# SCH_Konwerter-Hal-Elektrody_2026-02-04.net
KiCad netlist of a schematic drawn in EasyEDA
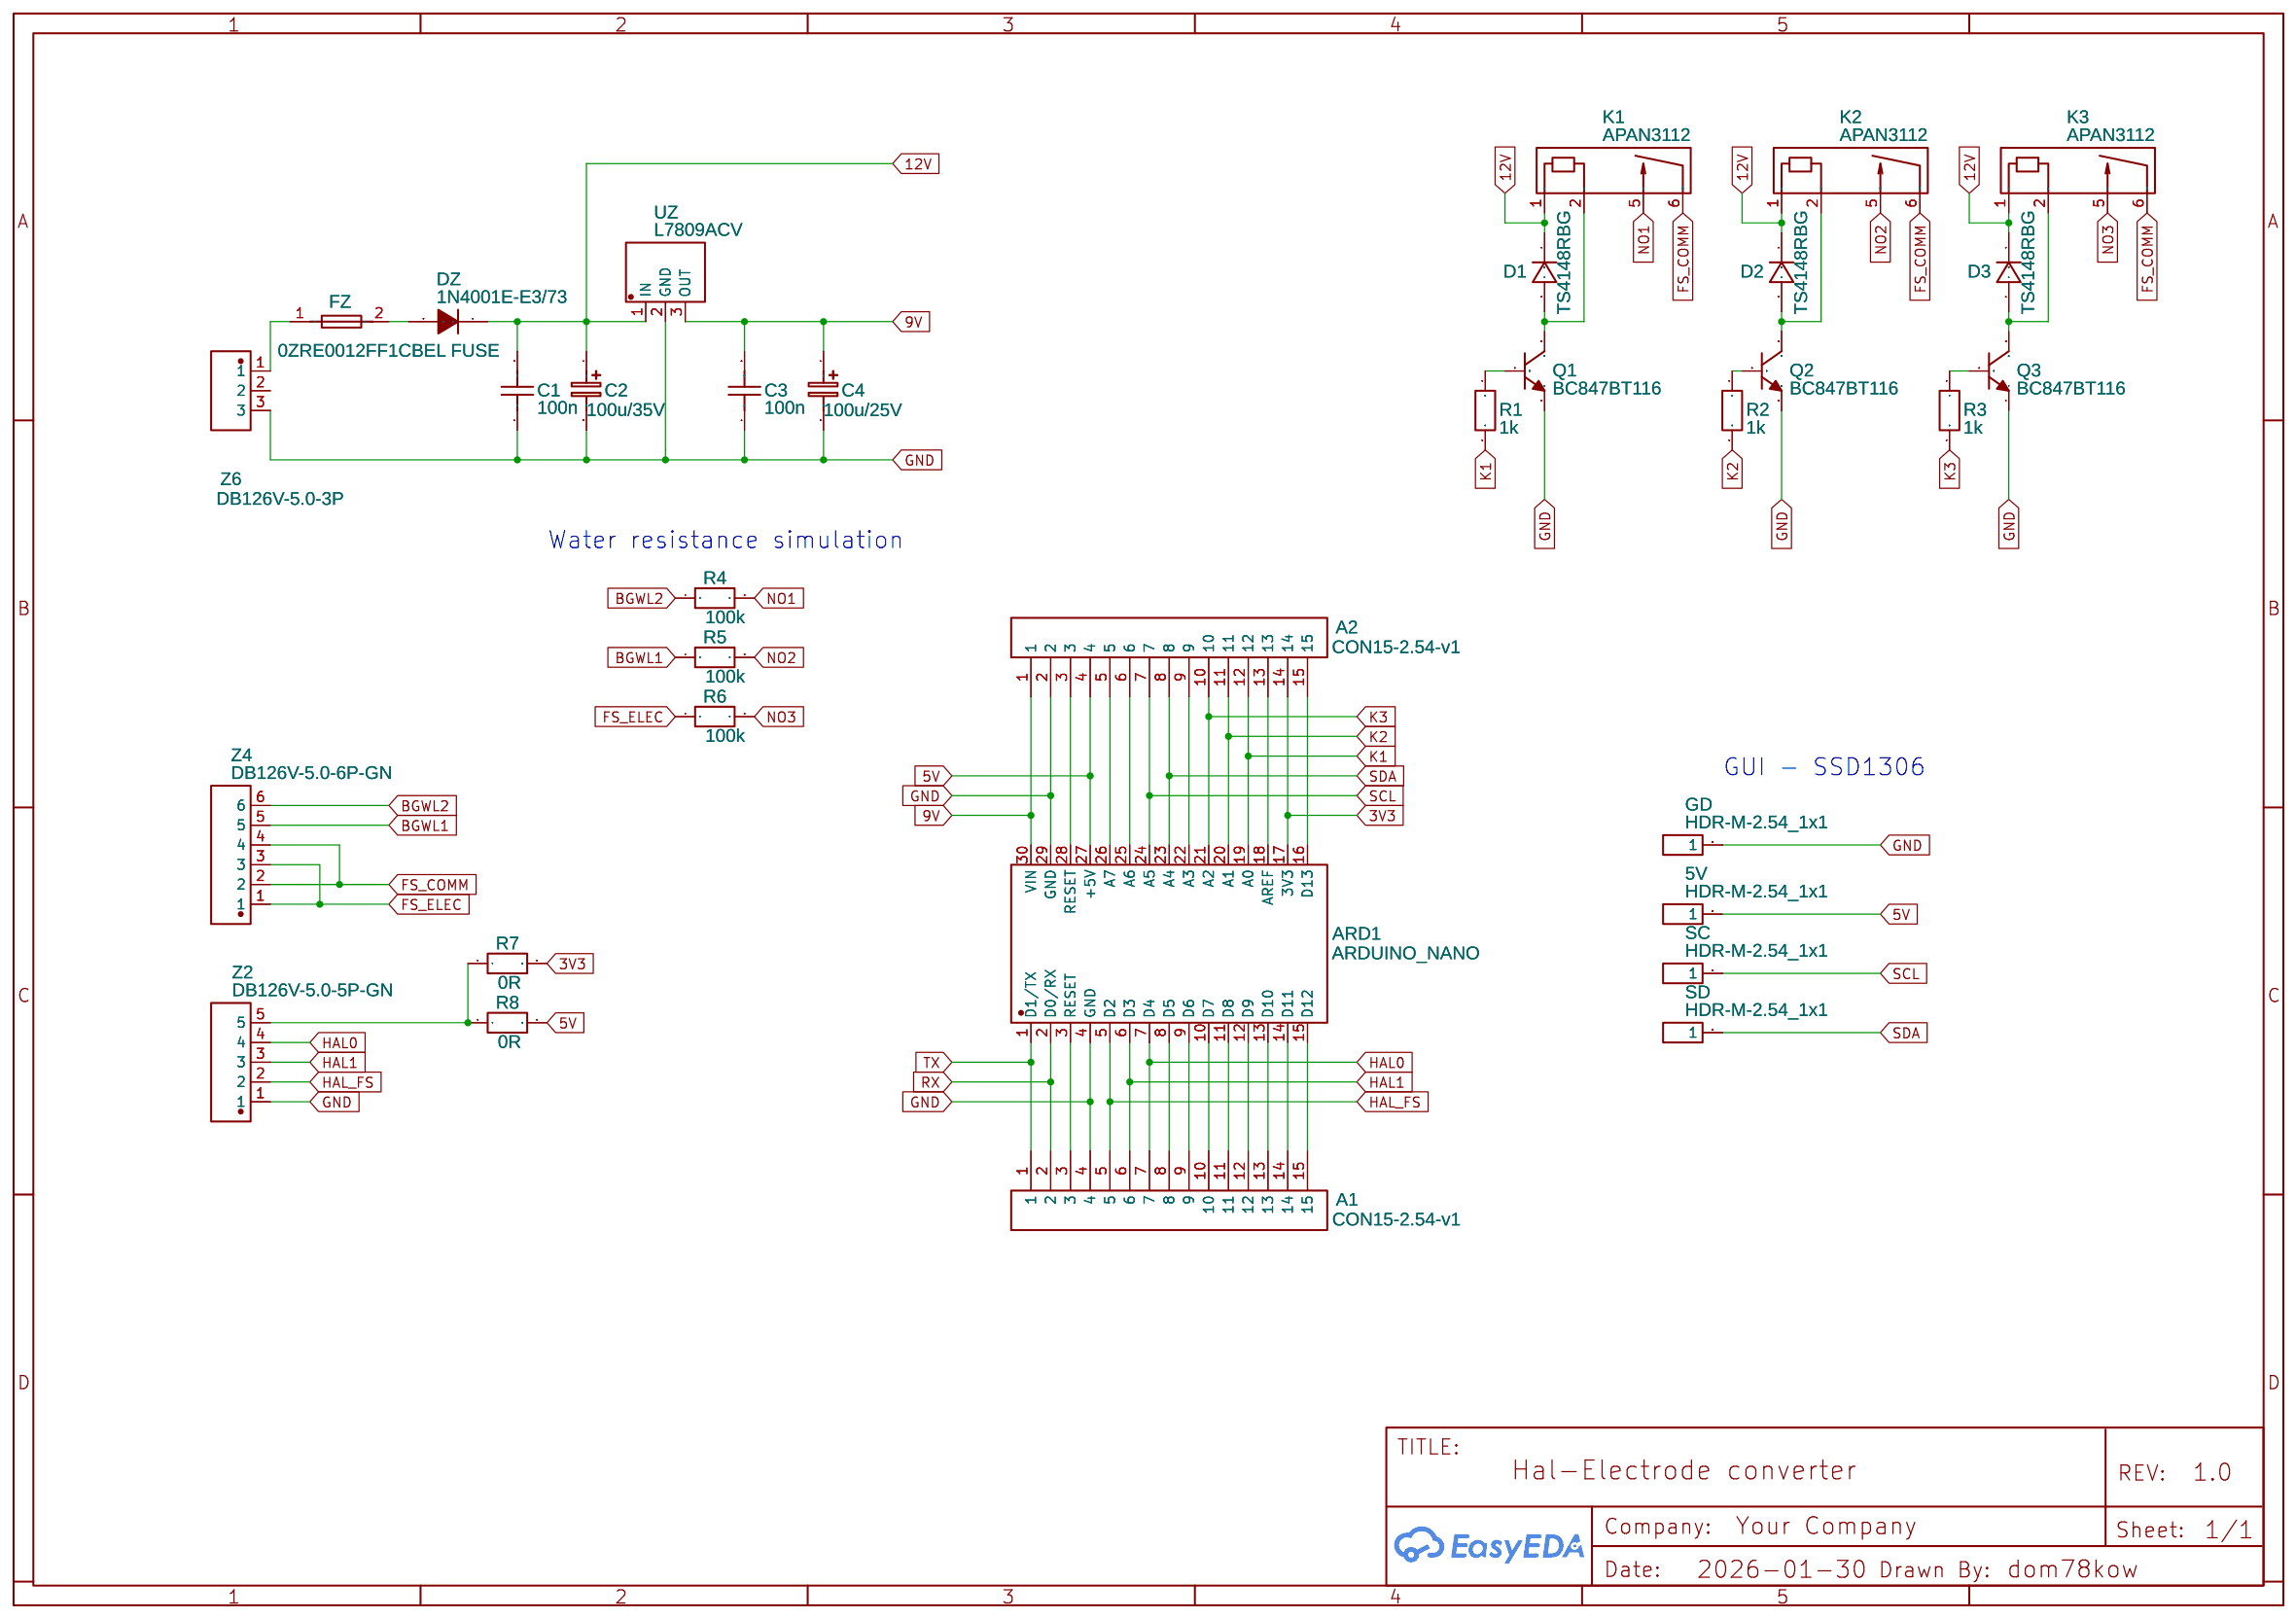
[diagram p0: schematic sheet]

(export (version "E")
  (design (tool "Eeschema 10.0.6"))
  (components
    (comp (ref "5V") (value "HDR-M-2.54_1x1") (libsource (lib "") (part "HDR-M-2.54_1x1_3")))
    (comp (ref "A1") (value "CON15-2.54-v1") (libsource (lib "") (part "CON15-2.54-v1_1")))
    (comp (ref "A2") (value "CON15-2.54-v1") (libsource (lib "") (part "CON15-2.54-v1")))
    (comp (ref "ARD1") (value "ARDUINO_NANO") (libsource (lib "") (part "ARDUINO_NANO")))
    (comp (ref "C1") (value "100n") (libsource (lib "") (part "C_1206_US")))
    (comp (ref "C2") (value "100u/35V") (libsource (lib "") (part "CE_TH_D5.0×F2.0_EU")))
    (comp (ref "C3") (value "100n") (libsource (lib "") (part "C_1206_US")))
    (comp (ref "C4") (value "100u/25V") (libsource (lib "") (part "CE_TH_D5.0×F2.0_EU")))
    (comp (ref "D1")
      (value "TS4148RBG")
      (fields (field (name "Manufacturer Part") "CD4148WP") (field (name "Manufacturer") "SUP(美隆)"))
      (libsource (lib "") (part "CD4148WP_C112371"))
    )
    (comp (ref "D2")
      (value "TS4148RBG")
      (fields (field (name "Manufacturer Part") "CD4148WP") (field (name "Manufacturer") "SUP(美隆)"))
      (libsource (lib "") (part "CD4148WP_C112371"))
    )
    (comp (ref "D3")
      (value "TS4148RBG")
      (fields (field (name "Manufacturer Part") "CD4148WP") (field (name "Manufacturer") "SUP(美隆)"))
      (libsource (lib "") (part "CD4148WP_C112371"))
    )
    (comp (ref "DZ")
      (value "1N4001E-E3/73")
      (fields (field (name "Manufacturer") "VISHAY(威世)"))
      (libsource (lib "") (part "1N4001E-E3/73"))
    )
    (comp (ref "FZ")
      (value "0ZRE0012FF1CBEL FUSE")
      (fields (field (name "Manufacturer Part") "SCT 2.5A") (field (name "Manufacturer") "Skygate(天宇匹克)"))
      (libsource (lib "") (part "SCT 2.5A"))
    )
    (comp (ref "GD") (value "HDR-M-2.54_1x1") (libsource (lib "") (part "HDR-M-2.54_1x1_1")))
    (comp (ref "K1")
      (value "APAN3112")
      (fields (field (name "Manufacturer Part") "APAN3105") (field (name "Manufacturer") "PANASONIC(松下)"))
      (libsource (lib "") (part "APAN3105"))
    )
    (comp (ref "K2")
      (value "APAN3112")
      (fields (field (name "Manufacturer Part") "APAN3105") (field (name "Manufacturer") "PANASONIC(松下)"))
      (libsource (lib "") (part "APAN3105"))
    )
    (comp (ref "K3")
      (value "APAN3112")
      (fields (field (name "Manufacturer Part") "APAN3105") (field (name "Manufacturer") "PANASONIC(松下)"))
      (libsource (lib "") (part "APAN3105"))
    )
    (comp (ref "Q1")
      (value "BC847BT116")
      (fields (field (name "Manufacturer") "ROHM(罗姆)"))
      (libsource (lib "") (part "BC847BT116"))
    )
    (comp (ref "Q2")
      (value "BC847BT116")
      (fields (field (name "Manufacturer") "ROHM(罗姆)"))
      (libsource (lib "") (part "BC847BT116"))
    )
    (comp (ref "Q3")
      (value "BC847BT116")
      (fields (field (name "Manufacturer") "ROHM(罗姆)"))
      (libsource (lib "") (part "BC847BT116"))
    )
    (comp (ref "R1") (value "1k") (libsource (lib "") (part "R_1206_EU_1")))
    (comp (ref "R2") (value "1k") (libsource (lib "") (part "R_1206_EU_1")))
    (comp (ref "R3") (value "1k") (libsource (lib "") (part "R_1206_EU_1")))
    (comp (ref "R4") (value "100k") (libsource (lib "") (part "R_1206_EU")))
    (comp (ref "R5") (value "100k") (libsource (lib "") (part "R_1206_EU")))
    (comp (ref "R6") (value "100k") (libsource (lib "") (part "R_1206_EU")))
    (comp (ref "R7") (value "0R") (libsource (lib "") (part "R_1206_EU")))
    (comp (ref "R8") (value "0R") (libsource (lib "") (part "R_1206_EU")))
    (comp (ref "SC") (value "HDR-M-2.54_1x1") (libsource (lib "") (part "HDR-M-2.54_1x1")))
    (comp (ref "SD") (value "HDR-M-2.54_1x1") (libsource (lib "") (part "HDR-M-2.54_1x1_2")))
    (comp (ref "UZ")
      (value "L7809ACV")
      (fields (field (name "Manufacturer Part") "L7812ACV") (field (name "Manufacturer") "ST(意法半导体)"))
      (libsource (lib "") (part "L7812ACV"))
    )
    (comp (ref "Z2")
      (value "DB126V-5.0-5P-GN")
      (fields
        (field (name "Manufacturer Part") "DB126V-5.0-5P-GN-P")
        (field (name "Manufacturer") "DIBO(地博电气)")
      )
      (libsource (lib "") (part "DB126V-5.0-5P-GN"))
    )
    (comp (ref "Z4")
      (value "DB126V-5.0-6P-GN")
      (fields
        (field (name "Manufacturer Part") "DB126V-5.0-6P-GN-P")
        (field (name "Manufacturer") "DORABO(地博电气)")
      )
      (libsource (lib "") (part "DB126V-5.0-6P-GN"))
    )
    (comp (ref "Z6")
      (value "DB126V-5.0-3P")
      (fields
        (field (name "Manufacturer Part") "DB126V-5.0-3P-GN")
        (field (name "Manufacturer") "DORABO(地博电气)")
      )
      (libsource (lib "") (part "DB126V-5.0-3P"))
    )
  )
  (nets
    (net (code "1") (name "3V3") (class "Default")
      (node (ref "A2") (pin "14") (pinfunction "14_14") (pintype "unspecified"))
      (node (ref "ARD1") (pin "17") (pinfunction "3V3_17") (pintype "unspecified"))
      (node (ref "R7") (pin "2") (pinfunction "2_2") (pintype "unspecified"))
    )
    (net (code "2") (name "5V") (class "Default")
      (node (ref "5V") (pin "1") (pinfunction "1_1") (pintype "input"))
      (node (ref "A2") (pin "4") (pinfunction "4_4") (pintype "unspecified"))
      (node (ref "ARD1") (pin "27") (pinfunction "+5V_27") (pintype "unspecified"))
      (node (ref "R8") (pin "2") (pinfunction "2_2") (pintype "unspecified"))
    )
    (net (code "3") (name "9V") (class "Default")
      (node (ref "A2") (pin "1") (pinfunction "1_1") (pintype "unspecified"))
      (node (ref "ARD1") (pin "30") (pinfunction "VIN_30") (pintype "unspecified"))
      (node (ref "C3") (pin "2") (pinfunction "2_2") (pintype "unspecified"))
      (node (ref "C4") (pin "1") (pinfunction "1_1") (pintype "unspecified"))
      (node (ref "UZ") (pin "3") (pinfunction "OUT_3") (pintype "unspecified"))
    )
    (net (code "4") (name "12V") (class "Default")
      (node (ref "C1") (pin "2") (pinfunction "2_2") (pintype "unspecified"))
      (node (ref "C2") (pin "1") (pinfunction "1_1") (pintype "unspecified"))
      (node (ref "D1") (pin "1") (pinfunction "C_1") (pintype "unspecified"))
      (node (ref "D2") (pin "1") (pinfunction "C_1") (pintype "unspecified"))
      (node (ref "D3") (pin "1") (pinfunction "C_1") (pintype "unspecified"))
      (node (ref "DZ") (pin "1") (pinfunction "K_1") (pintype "unspecified"))
      (node (ref "K1") (pin "1") (pinfunction "1_1") (pintype "unspecified"))
      (node (ref "K2") (pin "1") (pinfunction "1_1") (pintype "unspecified"))
      (node (ref "K3") (pin "1") (pinfunction "1_1") (pintype "unspecified"))
      (node (ref "UZ") (pin "1") (pinfunction "IN_1") (pintype "unspecified"))
    )
    (net (code "5") (name "BGWL1") (class "Default")
      (node (ref "R5") (pin "1") (pinfunction "1_1") (pintype "unspecified"))
      (node (ref "Z4") (pin "5") (pinfunction "5_5") (pintype "unspecified"))
    )
    (net (code "6") (name "BGWL2") (class "Default")
      (node (ref "R4") (pin "1") (pinfunction "1_1") (pintype "unspecified"))
      (node (ref "Z4") (pin "6") (pinfunction "6_6") (pintype "unspecified"))
    )
    (net (code "7") (name "FS_COMM") (class "Default")
      (node (ref "K1") (pin "6") (pinfunction "COM_6") (pintype "unspecified"))
      (node (ref "K2") (pin "6") (pinfunction "COM_6") (pintype "unspecified"))
      (node (ref "K3") (pin "6") (pinfunction "COM_6") (pintype "unspecified"))
      (node (ref "Z4") (pin "2") (pinfunction "2_2") (pintype "unspecified"))
      (node (ref "Z4") (pin "4") (pinfunction "4_4") (pintype "unspecified"))
    )
    (net (code "8") (name "FS_ELEC") (class "Default")
      (node (ref "R6") (pin "1") (pinfunction "1_1") (pintype "unspecified"))
      (node (ref "Z4") (pin "1") (pinfunction "1_1") (pintype "unspecified"))
      (node (ref "Z4") (pin "3") (pinfunction "3_3") (pintype "unspecified"))
    )
    (net (code "9") (name "GND") (class "Default")
      (node (ref "A1") (pin "4") (pinfunction "4_4") (pintype "unspecified"))
      (node (ref "A2") (pin "2") (pinfunction "2_2") (pintype "unspecified"))
      (node (ref "ARD1") (pin "29") (pinfunction "GND_29") (pintype "unspecified"))
      (node (ref "ARD1") (pin "4") (pinfunction "GND_4") (pintype "unspecified"))
      (node (ref "C1") (pin "1") (pinfunction "1_1") (pintype "unspecified"))
      (node (ref "C2") (pin "2") (pinfunction "2_2") (pintype "unspecified"))
      (node (ref "C3") (pin "1") (pinfunction "1_1") (pintype "unspecified"))
      (node (ref "C4") (pin "2") (pinfunction "2_2") (pintype "unspecified"))
      (node (ref "GD") (pin "1") (pinfunction "1_1") (pintype "input"))
      (node (ref "Q1") (pin "1") (pinfunction "E_1") (pintype "input"))
      (node (ref "Q2") (pin "1") (pinfunction "E_1") (pintype "input"))
      (node (ref "Q3") (pin "1") (pinfunction "E_1") (pintype "input"))
      (node (ref "UZ") (pin "2") (pinfunction "GND_2") (pintype "unspecified"))
      (node (ref "Z2") (pin "1") (pinfunction "1_1") (pintype "unspecified"))
      (node (ref "Z6") (pin "3") (pinfunction "3_3") (pintype "unspecified"))
    )
    (net (code "10") (name "HAL0") (class "Default")
      (node (ref "A1") (pin "7") (pinfunction "7_7") (pintype "unspecified"))
      (node (ref "ARD1") (pin "7") (pinfunction "D4_7") (pintype "unspecified"))
      (node (ref "Z2") (pin "4") (pinfunction "4_4") (pintype "unspecified"))
    )
    (net (code "11") (name "HAL1") (class "Default")
      (node (ref "A1") (pin "6") (pinfunction "6_6") (pintype "unspecified"))
      (node (ref "ARD1") (pin "6") (pinfunction "D3_6") (pintype "unspecified"))
      (node (ref "Z2") (pin "3") (pinfunction "3_3") (pintype "unspecified"))
    )
    (net (code "12") (name "HAL_FS") (class "Default")
      (node (ref "A1") (pin "5") (pinfunction "5_5") (pintype "unspecified"))
      (node (ref "ARD1") (pin "5") (pinfunction "D2_5") (pintype "unspecified"))
      (node (ref "Z2") (pin "2") (pinfunction "2_2") (pintype "unspecified"))
    )
    (net (code "13") (name "K1") (class "Default")
      (node (ref "A2") (pin "12") (pinfunction "12_12") (pintype "unspecified"))
      (node (ref "ARD1") (pin "19") (pinfunction "A0_19") (pintype "unspecified"))
      (node (ref "R1") (pin "2") (pinfunction "2_2") (pintype "unspecified"))
    )
    (net (code "14") (name "K2") (class "Default")
      (node (ref "A2") (pin "11") (pinfunction "11_11") (pintype "unspecified"))
      (node (ref "ARD1") (pin "20") (pinfunction "A1_20") (pintype "unspecified"))
      (node (ref "R2") (pin "2") (pinfunction "2_2") (pintype "unspecified"))
    )
    (net (code "15") (name "K3") (class "Default")
      (node (ref "A2") (pin "10") (pinfunction "10_10") (pintype "unspecified"))
      (node (ref "ARD1") (pin "21") (pinfunction "A2_21") (pintype "unspecified"))
      (node (ref "R3") (pin "2") (pinfunction "2_2") (pintype "unspecified"))
    )
    (net (code "16") (name "NO1") (class "Default")
      (node (ref "K1") (pin "5") (pinfunction "ON_5") (pintype "unspecified"))
      (node (ref "R4") (pin "2") (pinfunction "2_2") (pintype "unspecified"))
    )
    (net (code "17") (name "NO2") (class "Default")
      (node (ref "K2") (pin "5") (pinfunction "ON_5") (pintype "unspecified"))
      (node (ref "R5") (pin "2") (pinfunction "2_2") (pintype "unspecified"))
    )
    (net (code "18") (name "NO3") (class "Default")
      (node (ref "K3") (pin "5") (pinfunction "ON_5") (pintype "unspecified"))
      (node (ref "R6") (pin "2") (pinfunction "2_2") (pintype "unspecified"))
    )
    (net (code "19") (name "Net-(A1-Pad3)") (class "Default")
      (node (ref "A1") (pin "3") (pinfunction "3_3") (pintype "unspecified"))
      (node (ref "ARD1") (pin "3") (pinfunction "RESET_3") (pintype "unspecified"))
    )
    (net (code "20") (name "Net-(A2-Pad3)") (class "Default")
      (node (ref "A2") (pin "3") (pinfunction "3_3") (pintype "unspecified"))
      (node (ref "ARD1") (pin "28") (pinfunction "RESET_28") (pintype "unspecified"))
    )
    (net (code "21") (name "Net-(ARD1-A3)") (class "Default")
      (node (ref "A2") (pin "9") (pinfunction "9_9") (pintype "unspecified"))
      (node (ref "ARD1") (pin "22") (pinfunction "A3_22") (pintype "unspecified"))
    )
    (net (code "22") (name "Net-(ARD1-A6)") (class "Default")
      (node (ref "A2") (pin "6") (pinfunction "6_6") (pintype "unspecified"))
      (node (ref "ARD1") (pin "25") (pinfunction "A6_25") (pintype "unspecified"))
    )
    (net (code "23") (name "Net-(ARD1-A7)") (class "Default")
      (node (ref "A2") (pin "5") (pinfunction "5_5") (pintype "unspecified"))
      (node (ref "ARD1") (pin "26") (pinfunction "A7_26") (pintype "unspecified"))
    )
    (net (code "24") (name "Net-(ARD1-AREF)") (class "Default")
      (node (ref "A2") (pin "13") (pinfunction "13_13") (pintype "unspecified"))
      (node (ref "ARD1") (pin "18") (pinfunction "AREF_18") (pintype "unspecified"))
    )
    (net (code "25") (name "Net-(ARD1-D5)") (class "Default")
      (node (ref "A1") (pin "8") (pinfunction "8_8") (pintype "unspecified"))
      (node (ref "ARD1") (pin "8") (pinfunction "D5_8") (pintype "unspecified"))
    )
    (net (code "26") (name "Net-(ARD1-D6)") (class "Default")
      (node (ref "A1") (pin "9") (pinfunction "9_9") (pintype "unspecified"))
      (node (ref "ARD1") (pin "9") (pinfunction "D6_9") (pintype "unspecified"))
    )
    (net (code "27") (name "Net-(ARD1-D7)") (class "Default")
      (node (ref "A1") (pin "10") (pinfunction "10_10") (pintype "unspecified"))
      (node (ref "ARD1") (pin "10") (pinfunction "D7_10") (pintype "unspecified"))
    )
    (net (code "28") (name "Net-(ARD1-D8)") (class "Default")
      (node (ref "A1") (pin "11") (pinfunction "11_11") (pintype "unspecified"))
      (node (ref "ARD1") (pin "11") (pinfunction "D8_11") (pintype "unspecified"))
    )
    (net (code "29") (name "Net-(ARD1-D9)") (class "Default")
      (node (ref "A1") (pin "12") (pinfunction "12_12") (pintype "unspecified"))
      (node (ref "ARD1") (pin "12") (pinfunction "D9_12") (pintype "unspecified"))
    )
    (net (code "30") (name "Net-(ARD1-D10)") (class "Default")
      (node (ref "A1") (pin "13") (pinfunction "13_13") (pintype "unspecified"))
      (node (ref "ARD1") (pin "13") (pinfunction "D10_13") (pintype "unspecified"))
    )
    (net (code "31") (name "Net-(ARD1-D11)") (class "Default")
      (node (ref "A1") (pin "14") (pinfunction "14_14") (pintype "unspecified"))
      (node (ref "ARD1") (pin "14") (pinfunction "D11_14") (pintype "unspecified"))
    )
    (net (code "32") (name "Net-(ARD1-D12)") (class "Default")
      (node (ref "A1") (pin "15") (pinfunction "15_15") (pintype "unspecified"))
      (node (ref "ARD1") (pin "15") (pinfunction "D12_15") (pintype "unspecified"))
    )
    (net (code "33") (name "Net-(ARD1-D13)") (class "Default")
      (node (ref "A2") (pin "15") (pinfunction "15_15") (pintype "unspecified"))
      (node (ref "ARD1") (pin "16") (pinfunction "D13_16") (pintype "unspecified"))
    )
    (net (code "34") (name "Net-(D1-A)") (class "Default")
      (node (ref "D1") (pin "2") (pinfunction "A_2") (pintype "unspecified"))
      (node (ref "K1") (pin "2") (pinfunction "2_2") (pintype "unspecified"))
      (node (ref "Q1") (pin "3") (pinfunction "C_3") (pintype "input"))
    )
    (net (code "35") (name "Net-(D2-A)") (class "Default")
      (node (ref "D2") (pin "2") (pinfunction "A_2") (pintype "unspecified"))
      (node (ref "K2") (pin "2") (pinfunction "2_2") (pintype "unspecified"))
      (node (ref "Q2") (pin "3") (pinfunction "C_3") (pintype "input"))
    )
    (net (code "36") (name "Net-(D3-A)") (class "Default")
      (node (ref "D3") (pin "2") (pinfunction "A_2") (pintype "unspecified"))
      (node (ref "K3") (pin "2") (pinfunction "2_2") (pintype "unspecified"))
      (node (ref "Q3") (pin "3") (pinfunction "C_3") (pintype "input"))
    )
    (net (code "37") (name "Net-(DZ-A)") (class "Default")
      (node (ref "DZ") (pin "2") (pinfunction "A_2") (pintype "unspecified"))
      (node (ref "FZ") (pin "2") (pinfunction "2_2") (pintype "unspecified"))
    )
    (net (code "38") (name "Net-(FZ-Pad1)") (class "Default")
      (node (ref "FZ") (pin "1") (pinfunction "1_1") (pintype "unspecified"))
      (node (ref "Z6") (pin "1") (pinfunction "1_1") (pintype "unspecified"))
    )
    (net (code "39") (name "Net-(Q1-B)") (class "Default")
      (node (ref "Q1") (pin "2") (pinfunction "B_2") (pintype "input"))
      (node (ref "R1") (pin "1") (pinfunction "1_1") (pintype "unspecified"))
    )
    (net (code "40") (name "Net-(Q2-B)") (class "Default")
      (node (ref "Q2") (pin "2") (pinfunction "B_2") (pintype "input"))
      (node (ref "R2") (pin "1") (pinfunction "1_1") (pintype "unspecified"))
    )
    (net (code "41") (name "Net-(Q3-B)") (class "Default")
      (node (ref "Q3") (pin "2") (pinfunction "B_2") (pintype "input"))
      (node (ref "R3") (pin "1") (pinfunction "1_1") (pintype "unspecified"))
    )
    (net (code "42") (name "Net-(R7-Pad1)") (class "Default")
      (node (ref "R7") (pin "1") (pinfunction "1_1") (pintype "unspecified"))
      (node (ref "R8") (pin "1") (pinfunction "1_1") (pintype "unspecified"))
      (node (ref "Z2") (pin "5") (pinfunction "5_5") (pintype "unspecified"))
    )
    (net (code "43") (name "RX") (class "Default")
      (node (ref "A1") (pin "2") (pinfunction "2_2") (pintype "unspecified"))
      (node (ref "ARD1") (pin "2") (pinfunction "D0/RX_2") (pintype "unspecified"))
    )
    (net (code "44") (name "SCL") (class "Default")
      (node (ref "A2") (pin "7") (pinfunction "7_7") (pintype "unspecified"))
      (node (ref "ARD1") (pin "24") (pinfunction "A5_24") (pintype "unspecified"))
      (node (ref "SC") (pin "1") (pinfunction "1_1") (pintype "input"))
    )
    (net (code "45") (name "SDA") (class "Default")
      (node (ref "A2") (pin "8") (pinfunction "8_8") (pintype "unspecified"))
      (node (ref "ARD1") (pin "23") (pinfunction "A4_23") (pintype "unspecified"))
      (node (ref "SD") (pin "1") (pinfunction "1_1") (pintype "input"))
    )
    (net (code "46") (name "TX") (class "Default")
      (node (ref "A1") (pin "1") (pinfunction "1_1") (pintype "unspecified"))
      (node (ref "ARD1") (pin "1") (pinfunction "D1/TX_1") (pintype "unspecified"))
    )
    (net (code "47") (name "unconnected-(Z6-Pad2)") (class "Default")
      (node (ref "Z6") (pin "2") (pinfunction "2_2") (pintype "unspecified"))
    )
  )
)
